# SCH_Linefollowerv1_2022-10-21.net
KiCad netlist of a schematic drawn in EasyEDA
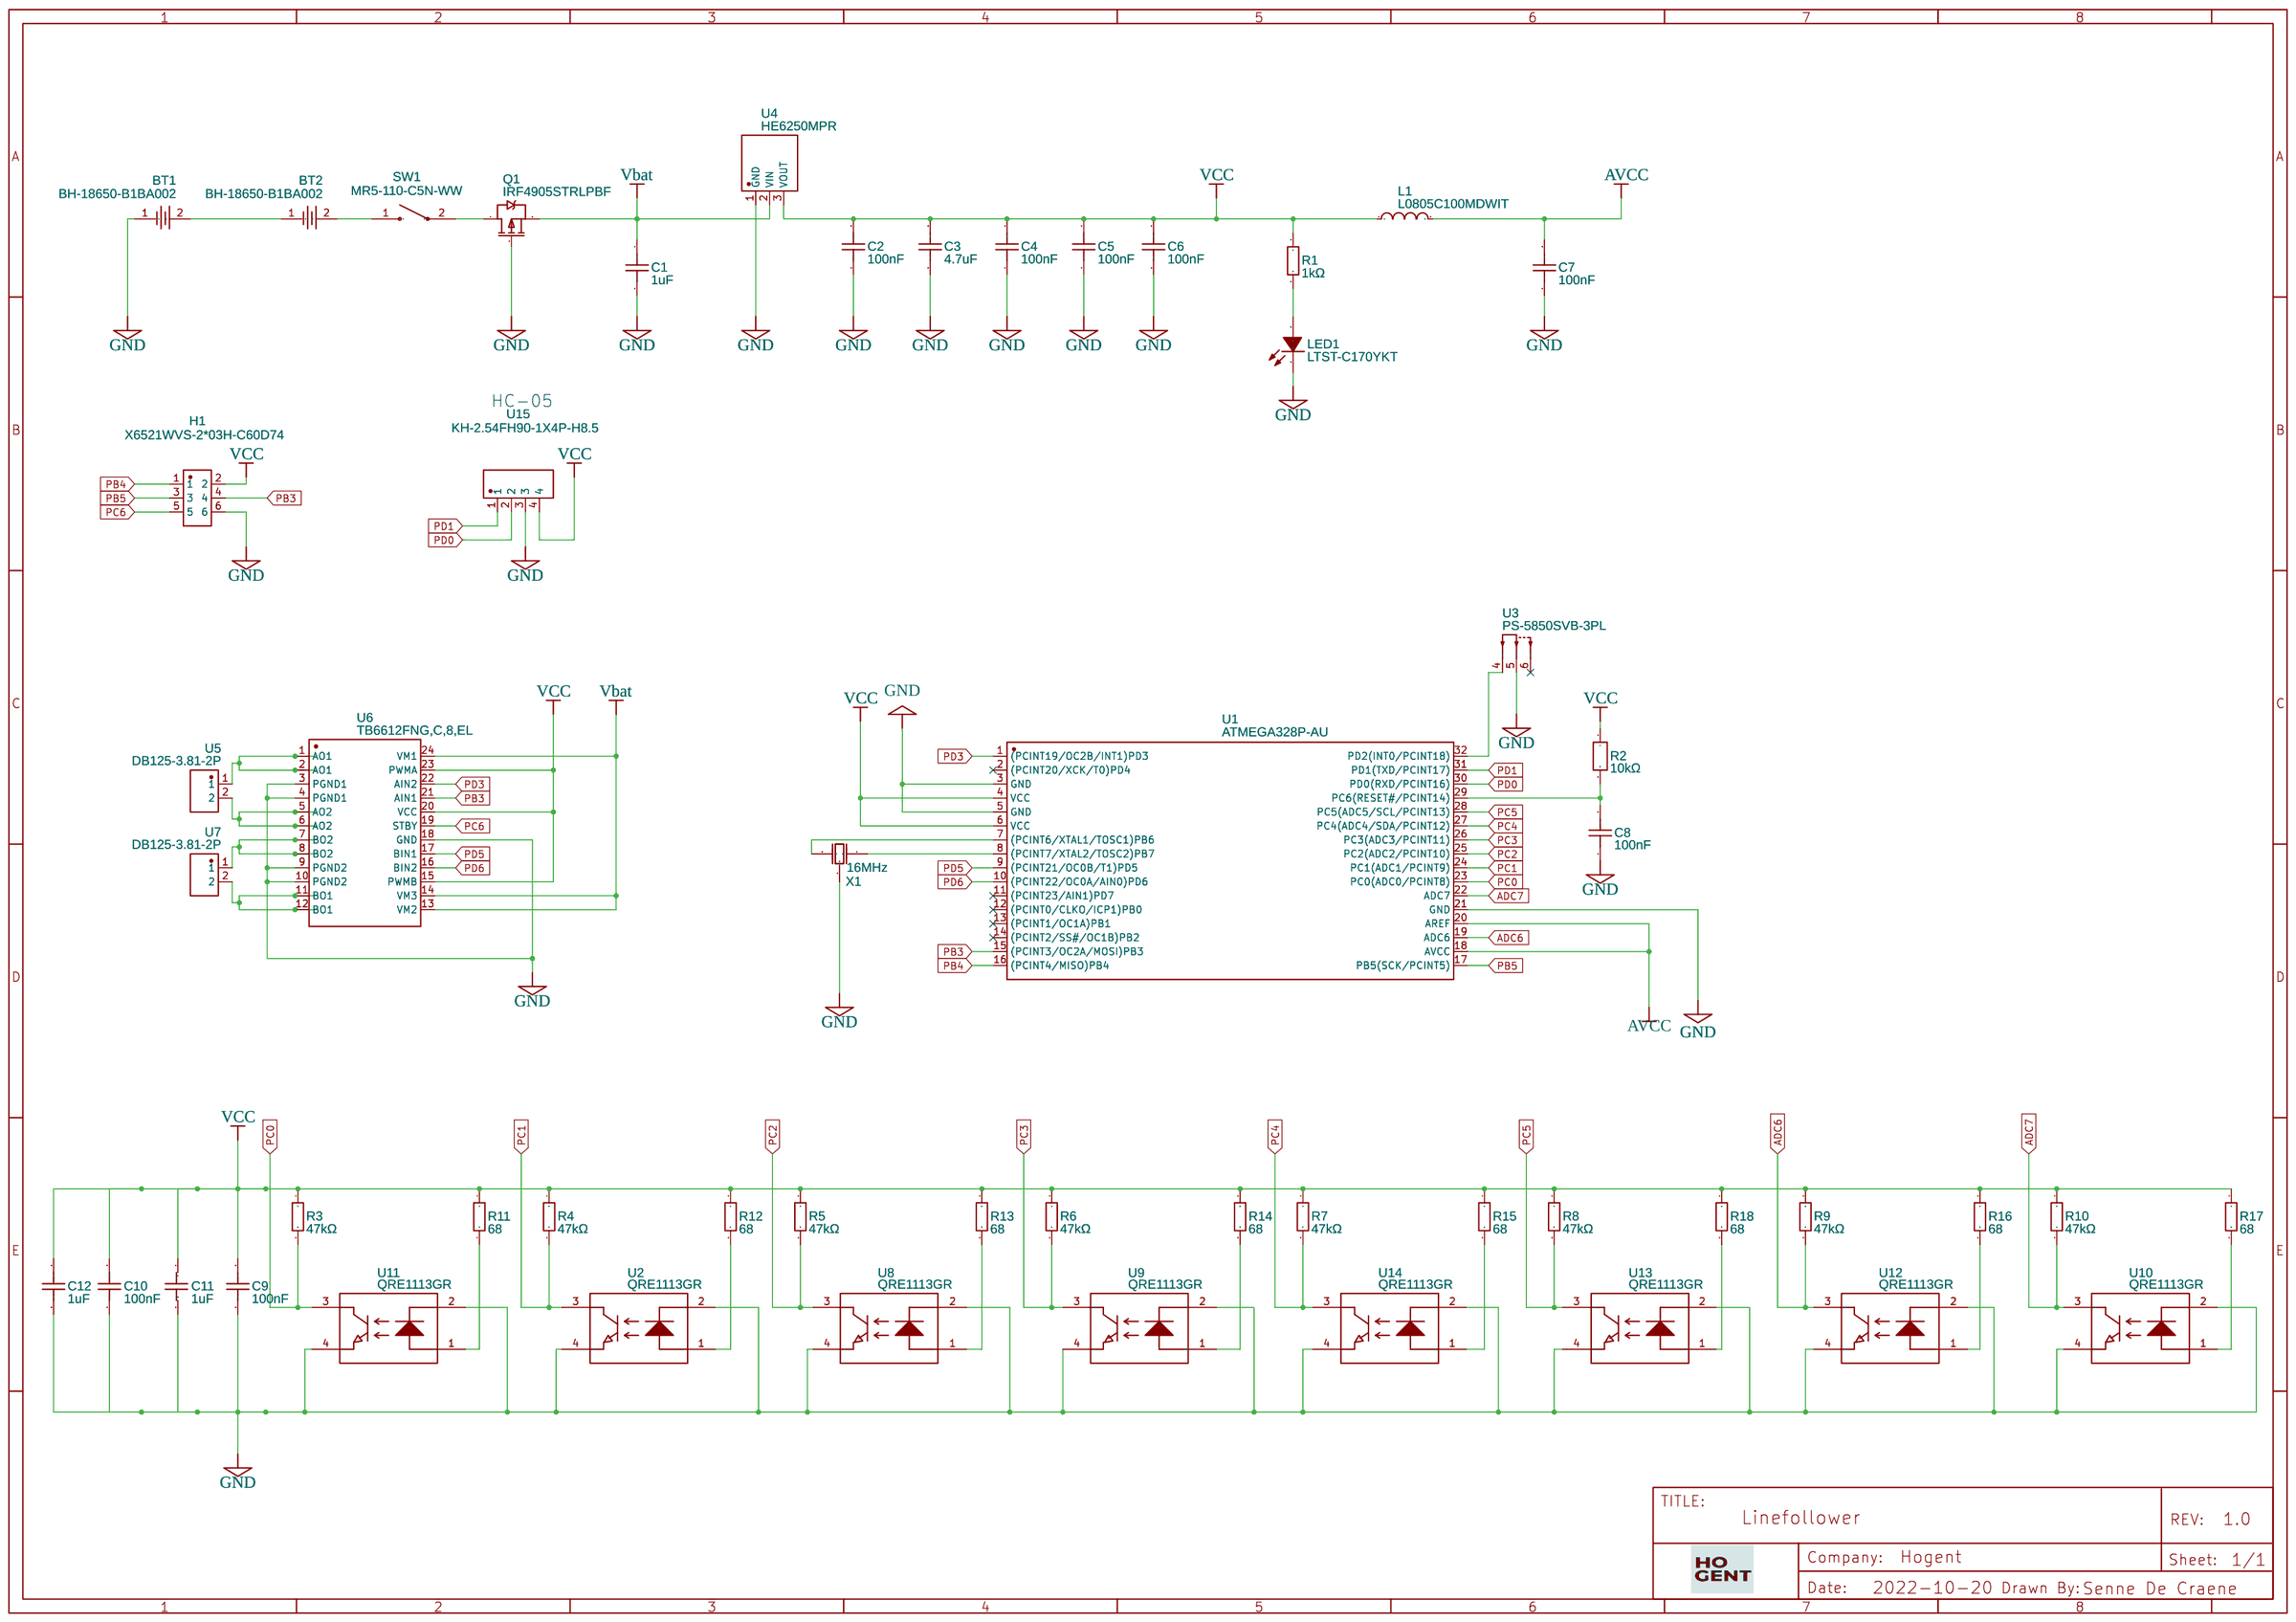
[diagram p0: schematic sheet]

(export (version "E")
  (design (tool "Eeschema 10.0.6"))
  (components
    (comp (ref "BT1")
      (value "BH-18650-B1BA002")
      (fields (field (name "BOM_Supplier Part") "C2988620"))
      (libsource (lib "") (part "BH-18650-B1BA002"))
    )
    (comp (ref "BT2")
      (value "BH-18650-B1BA002")
      (fields (field (name "BOM_Supplier Part") "C2988620"))
      (libsource (lib "") (part "BH-18650-B1BA002"))
    )
    (comp (ref "C1")
      (value "1uF")
      (fields
        (field (name "BOM_Manufacturer Part") "LMK212BJ105KD-T")
        (field (name "BOM_Supplier Part") "C92812")
      )
      (libsource (lib "") (part "LMK212BJ105KD-T_1"))
    )
    (comp (ref "C2")
      (value "100nF")
      (fields
        (field (name "BOM_Manufacturer Part") "LMK212SD104KG-T")
        (field (name "BOM_Supplier Part") "C386062")
      )
      (libsource (lib "") (part "LMK212SD104KG-T"))
    )
    (comp (ref "C3")
      (value "4.7uF")
      (fields
        (field (name "BOM_Manufacturer Part") "GCM21BC71A475KA73L")
        (field (name "BOM_Supplier Part") "C126583")
      )
      (libsource (lib "") (part "GCM21BC71A475KA73L"))
    )
    (comp (ref "C4")
      (value "100nF")
      (fields
        (field (name "BOM_Manufacturer Part") "LMK212SD104KG-T")
        (field (name "BOM_Supplier Part") "C386062")
      )
      (libsource (lib "") (part "LMK212SD104KG-T"))
    )
    (comp (ref "C5")
      (value "100nF")
      (fields
        (field (name "BOM_Manufacturer Part") "LMK212SD104KG-T")
        (field (name "BOM_Supplier Part") "C386062")
      )
      (libsource (lib "") (part "LMK212SD104KG-T"))
    )
    (comp (ref "C6")
      (value "100nF")
      (fields
        (field (name "BOM_Manufacturer Part") "LMK212SD104KG-T")
        (field (name "BOM_Supplier Part") "C386062")
      )
      (libsource (lib "") (part "LMK212SD104KG-T"))
    )
    (comp (ref "C7")
      (value "100nF")
      (fields
        (field (name "BOM_Manufacturer Part") "LMK212SD104KG-T")
        (field (name "BOM_Supplier Part") "C386062")
      )
      (libsource (lib "") (part "LMK212SD104KG-T"))
    )
    (comp (ref "C8")
      (value "100nF")
      (fields
        (field (name "BOM_Manufacturer Part") "LMK212SD104KG-T")
        (field (name "BOM_Supplier Part") "C386062")
      )
      (libsource (lib "") (part "LMK212SD104KG-T"))
    )
    (comp (ref "C9")
      (value "100nF")
      (fields
        (field (name "BOM_Manufacturer Part") "LMK212SD104KG-T")
        (field (name "BOM_Supplier Part") "C386062")
      )
      (libsource (lib "") (part "LMK212SD104KG-T"))
    )
    (comp (ref "C10")
      (value "100nF")
      (fields
        (field (name "BOM_Manufacturer Part") "LMK212SD104KG-T")
        (field (name "BOM_Supplier Part") "C386062")
      )
      (libsource (lib "") (part "LMK212SD104KG-T"))
    )
    (comp (ref "C11")
      (value "1uF")
      (fields
        (field (name "BOM_Manufacturer Part") "LMK212BJ105KD-T")
        (field (name "BOM_Supplier Part") "C92812")
      )
      (libsource (lib "") (part "LMK212BJ105KD-T"))
    )
    (comp (ref "C12")
      (value "1uF")
      (fields
        (field (name "BOM_Manufacturer Part") "LMK212BJ105KD-T")
        (field (name "BOM_Supplier Part") "C92812")
      )
      (libsource (lib "") (part "LMK212BJ105KD-T_1"))
    )
    (comp (ref "H1")
      (value "X6521WVS-2*03H-C60D74")
      (fields (field (name "BOM_Supplier Part") "C780054"))
      (libsource (lib "") (part "X6521WVS-2*03H-C60D74"))
    )
    (comp (ref "L1")
      (value "L0805C100MDWIT")
      (fields (field (name "BOM_Supplier Part") "C696787"))
      (libsource (lib "") (part "L0805C100MDWIT"))
    )
    (comp (ref "LED1")
      (value "LTST-C170YKT")
      (fields (field (name "BOM_Supplier Part") "C125092"))
      (libsource (lib "") (part "LTST-C170YKT"))
    )
    (comp (ref "Q1")
      (value "IRF4905STRLPBF")
      (fields (field (name "BOM_Supplier Part") "C2620"))
      (libsource (lib "") (part "IRF4905STRLPBF"))
    )
    (comp (ref "R1")
      (value "1kΩ")
      (fields
        (field (name "BOM_Manufacturer Part") "ARG05BTC1001")
        (field (name "BOM_Supplier Part") "C309081")
      )
      (libsource (lib "") (part "ARG05BTC1001"))
    )
    (comp (ref "R2")
      (value "10kΩ")
      (fields
        (field (name "BOM_Manufacturer Part") "ARG05BTC1002")
        (field (name "BOM_Supplier Part") "C406725")
      )
      (libsource (lib "") (part "ARG05BTC1002"))
    )
    (comp (ref "R3")
      (value "47kΩ")
      (fields
        (field (name "BOM_Manufacturer Part") "AECR0805F47K0K9")
        (field (name "BOM_Supplier Part") "C328397")
      )
      (libsource (lib "") (part "AECR0805F47K0K9"))
    )
    (comp (ref "R4")
      (value "47kΩ")
      (fields
        (field (name "BOM_Manufacturer Part") "AECR0805F47K0K9")
        (field (name "BOM_Supplier Part") "C328397")
      )
      (libsource (lib "") (part "AECR0805F47K0K9"))
    )
    (comp (ref "R5")
      (value "47kΩ")
      (fields
        (field (name "BOM_Manufacturer Part") "AECR0805F47K0K9")
        (field (name "BOM_Supplier Part") "C328397")
      )
      (libsource (lib "") (part "AECR0805F47K0K9"))
    )
    (comp (ref "R6")
      (value "47kΩ")
      (fields
        (field (name "BOM_Manufacturer Part") "AECR0805F47K0K9")
        (field (name "BOM_Supplier Part") "C328397")
      )
      (libsource (lib "") (part "AECR0805F47K0K9"))
    )
    (comp (ref "R7")
      (value "47kΩ")
      (fields
        (field (name "BOM_Manufacturer Part") "AECR0805F47K0K9")
        (field (name "BOM_Supplier Part") "C328397")
      )
      (libsource (lib "") (part "AECR0805F47K0K9"))
    )
    (comp (ref "R8")
      (value "47kΩ")
      (fields
        (field (name "BOM_Manufacturer Part") "AECR0805F47K0K9")
        (field (name "BOM_Supplier Part") "C328397")
      )
      (libsource (lib "") (part "AECR0805F47K0K9"))
    )
    (comp (ref "R9")
      (value "47kΩ")
      (fields
        (field (name "BOM_Manufacturer Part") "AECR0805F47K0K9")
        (field (name "BOM_Supplier Part") "C328397")
      )
      (libsource (lib "") (part "AECR0805F47K0K9"))
    )
    (comp (ref "R10")
      (value "47kΩ")
      (fields
        (field (name "BOM_Manufacturer Part") "AECR0805F47K0K9")
        (field (name "BOM_Supplier Part") "C328397")
      )
      (libsource (lib "") (part "AECR0805F47K0K9"))
    )
    (comp (ref "R11")
      (value "68")
      (fields
        (field (name "BOM_Manufacturer Part") "RC0805FR-0768RL")
        (field (name "BOM_Supplier Part") "C137498")
      )
      (libsource (lib "") (part "RC0805FR-0768RL"))
    )
    (comp (ref "R12")
      (value "68")
      (fields
        (field (name "BOM_Manufacturer Part") "RC0805FR-0768RL")
        (field (name "BOM_Supplier Part") "C137498")
      )
      (libsource (lib "") (part "RC0805FR-0768RL"))
    )
    (comp (ref "R13")
      (value "68")
      (fields
        (field (name "BOM_Manufacturer Part") "RC0805FR-0768RL")
        (field (name "BOM_Supplier Part") "C137498")
      )
      (libsource (lib "") (part "RC0805FR-0768RL"))
    )
    (comp (ref "R14")
      (value "68")
      (fields
        (field (name "BOM_Manufacturer Part") "RC0805FR-0768RL")
        (field (name "BOM_Supplier Part") "C137498")
      )
      (libsource (lib "") (part "RC0805FR-0768RL"))
    )
    (comp (ref "R15")
      (value "68")
      (fields
        (field (name "BOM_Manufacturer Part") "RC0805FR-0768RL")
        (field (name "BOM_Supplier Part") "C137498")
      )
      (libsource (lib "") (part "RC0805FR-0768RL"))
    )
    (comp (ref "R16")
      (value "68")
      (fields
        (field (name "BOM_Manufacturer Part") "RC0805FR-0768RL")
        (field (name "BOM_Supplier Part") "C137498")
      )
      (libsource (lib "") (part "RC0805FR-0768RL"))
    )
    (comp (ref "R17")
      (value "68")
      (fields
        (field (name "BOM_Manufacturer Part") "RC0805FR-0768RL")
        (field (name "BOM_Supplier Part") "C137498")
      )
      (libsource (lib "") (part "RC0805FR-0768RL"))
    )
    (comp (ref "R18")
      (value "68")
      (fields
        (field (name "BOM_Manufacturer Part") "RC0805FR-0768RL")
        (field (name "BOM_Supplier Part") "C137498")
      )
      (libsource (lib "") (part "RC0805FR-0768RL"))
    )
    (comp (ref "SW1")
      (value "MR5-110-C5N-WW")
      (fields (field (name "BOM_Supplier Part") "C2829507"))
      (libsource (lib "") (part "MR5-110-C5N-WW"))
    )
    (comp (ref "U1")
      (value "ATMEGA328P-AU")
      (fields (field (name "BOM_Supplier Part") "C14877"))
      (libsource (lib "") (part "ATMEGA328P-AU"))
    )
    (comp (ref "U2")
      (value "QRE1113GR")
      (fields (field (name "BOM_Supplier Part") "C232862"))
      (libsource (lib "") (part "QRE1113GR_1"))
    )
    (comp (ref "U3")
      (value "PS-5850SVB-3PL")
      (fields (field (name "BOM_Supplier Part") "C5159077"))
      (libsource (lib "") (part "PS-5850SVB-3PL"))
    )
    (comp (ref "U4")
      (value "HE6250MPR")
      (fields (field (name "BOM_Supplier Part") "C711940"))
      (libsource (lib "") (part "HE6250MPR"))
    )
    (comp (ref "U5")
      (value "DB125-3.81-2P")
      (fields (field (name "BOM_Supplier Part") "C395878"))
      (libsource (lib "") (part "DB125-3.81-2P"))
    )
    (comp (ref "U6")
      (value "TB6612FNG,C,8,EL")
      (fields (field (name "BOM_Supplier Part") "C141517"))
      (libsource (lib "") (part "Unknown_500_-570"))
    )
    (comp (ref "U7")
      (value "DB125-3.81-2P")
      (fields (field (name "BOM_Supplier Part") "C395878"))
      (libsource (lib "") (part "DB125-3.81-2P"))
    )
    (comp (ref "U8")
      (value "QRE1113GR")
      (fields (field (name "BOM_Supplier Part") "C232862"))
      (libsource (lib "") (part "QRE1113GR_2"))
    )
    (comp (ref "U9")
      (value "QRE1113GR")
      (fields (field (name "BOM_Supplier Part") "C232862"))
      (libsource (lib "") (part "QRE1113GR_3"))
    )
    (comp (ref "U10")
      (value "QRE1113GR")
      (fields (field (name "BOM_Supplier Part") "C232862"))
      (libsource (lib "") (part "QRE1113GR_4"))
    )
    (comp (ref "U11")
      (value "QRE1113GR")
      (fields (field (name "BOM_Supplier Part") "C232862"))
      (libsource (lib "") (part "QRE1113GR_4"))
    )
    (comp (ref "U12")
      (value "QRE1113GR")
      (fields (field (name "BOM_Supplier Part") "C232862"))
      (libsource (lib "") (part "QRE1113GR_5"))
    )
    (comp (ref "U13")
      (value "QRE1113GR")
      (fields (field (name "BOM_Supplier Part") "C232862"))
      (libsource (lib "") (part "QRE1113GR"))
    )
    (comp (ref "U14")
      (value "QRE1113GR")
      (fields (field (name "BOM_Supplier Part") "C232862"))
      (libsource (lib "") (part "QRE1113GR_6"))
    )
    (comp (ref "U15")
      (value "KH-2.54FH90-1X4P-H8.5")
      (fields (field (name "BOM_Supplier Part") "C2932680"))
      (libsource (lib "") (part "KH-2.54FH90-1X4P-H8.5"))
    )
    (comp (ref "X1")
      (value "16MHz")
      (fields
        (field (name "BOM_Manufacturer Part") "CSTNE16M0V53C000R0")
        (field (name "BOM_Supplier Part") "C882606")
      )
      (libsource (lib "") (part "CSTNE16M0V53C000R0"))
    )
  )
  (nets
    (net (code "1") (name "ADC6") (class "Default")
      (node (ref "R9") (pin "2") (pinfunction "2_2") (pintype "unspecified"))
      (node (ref "U1") (pin "19") (pinfunction "ADC6_19") (pintype "unspecified"))
      (node (ref "U12") (pin "3") (pinfunction "3_3") (pintype "input"))
    )
    (net (code "2") (name "ADC7") (class "Default")
      (node (ref "R10") (pin "2") (pinfunction "2_2") (pintype "unspecified"))
      (node (ref "U1") (pin "22") (pinfunction "ADC7_22") (pintype "unspecified"))
      (node (ref "U10") (pin "3") (pinfunction "3_3") (pintype "input"))
    )
    (net (code "3") (name "AVCC") (class "Default")
      (node (ref "C7") (pin "2") (pinfunction "2_2") (pintype "unspecified"))
      (node (ref "L1") (pin "2") (pinfunction "2_2") (pintype "unspecified"))
      (node (ref "U1") (pin "18") (pinfunction "AVCC_18") (pintype "unspecified"))
      (node (ref "U1") (pin "20") (pinfunction "AREF_20") (pintype "unspecified"))
    )
    (net (code "4") (name "GND") (class "Default")
      (node (ref "BT1") (pin "1") (pinfunction "1_1") (pintype "input"))
      (node (ref "C1") (pin "2") (pinfunction "2_2") (pintype "unspecified"))
      (node (ref "C10") (pin "1") (pinfunction "1_1") (pintype "unspecified"))
      (node (ref "C11") (pin "2") (pinfunction "2_2") (pintype "unspecified"))
      (node (ref "C12") (pin "2") (pinfunction "2_2") (pintype "unspecified"))
      (node (ref "C2") (pin "1") (pinfunction "1_1") (pintype "unspecified"))
      (node (ref "C3") (pin "1") (pinfunction "1_1") (pintype "unspecified"))
      (node (ref "C4") (pin "1") (pinfunction "1_1") (pintype "unspecified"))
      (node (ref "C5") (pin "1") (pinfunction "1_1") (pintype "unspecified"))
      (node (ref "C6") (pin "1") (pinfunction "1_1") (pintype "unspecified"))
      (node (ref "C7") (pin "1") (pinfunction "1_1") (pintype "unspecified"))
      (node (ref "C8") (pin "1") (pinfunction "1_1") (pintype "unspecified"))
      (node (ref "C9") (pin "1") (pinfunction "1_1") (pintype "unspecified"))
      (node (ref "H1") (pin "6") (pinfunction "6_6") (pintype "unspecified"))
      (node (ref "LED1") (pin "1") (pinfunction "1_1") (pintype "unspecified"))
      (node (ref "Q1") (pin "1") (pinfunction "G_1") (pintype "unspecified"))
      (node (ref "U1") (pin "21") (pinfunction "GND_21") (pintype "unspecified"))
      (node (ref "U1") (pin "3") (pinfunction "GND_3") (pintype "unspecified"))
      (node (ref "U1") (pin "5") (pinfunction "GND_5") (pintype "unspecified"))
      (node (ref "U10") (pin "2") (pinfunction "2_2") (pintype "input"))
      (node (ref "U10") (pin "4") (pinfunction "4_4") (pintype "input"))
      (node (ref "U11") (pin "2") (pinfunction "2_2") (pintype "input"))
      (node (ref "U11") (pin "4") (pinfunction "4_4") (pintype "input"))
      (node (ref "U12") (pin "2") (pinfunction "2_2") (pintype "input"))
      (node (ref "U12") (pin "4") (pinfunction "4_4") (pintype "input"))
      (node (ref "U13") (pin "2") (pinfunction "2_2") (pintype "input"))
      (node (ref "U13") (pin "4") (pinfunction "4_4") (pintype "input"))
      (node (ref "U14") (pin "2") (pinfunction "2_2") (pintype "input"))
      (node (ref "U14") (pin "4") (pinfunction "4_4") (pintype "input"))
      (node (ref "U15") (pin "3") (pinfunction "3_3") (pintype "unspecified"))
      (node (ref "U2") (pin "2") (pinfunction "2_2") (pintype "input"))
      (node (ref "U2") (pin "4") (pinfunction "4_4") (pintype "input"))
      (node (ref "U3") (pin "5") (pinfunction "5_5") (pintype "unspecified"))
      (node (ref "U4") (pin "1") (pinfunction "GND_1") (pintype "unspecified"))
      (node (ref "U6") (pin "10") (pinfunction "PGND2_10") (pintype "unspecified"))
      (node (ref "U6") (pin "18") (pinfunction "GND_18") (pintype "unspecified"))
      (node (ref "U6") (pin "3") (pinfunction "PGND1_3") (pintype "unspecified"))
      (node (ref "U6") (pin "4") (pinfunction "PGND1_4") (pintype "unspecified"))
      (node (ref "U6") (pin "9") (pinfunction "PGND2_9") (pintype "unspecified"))
      (node (ref "U8") (pin "2") (pinfunction "2_2") (pintype "input"))
      (node (ref "U8") (pin "4") (pinfunction "4_4") (pintype "input"))
      (node (ref "U9") (pin "2") (pinfunction "2_2") (pintype "input"))
      (node (ref "U9") (pin "4") (pinfunction "4_4") (pintype "input"))
      (node (ref "X1") (pin "2") (pinfunction "GND_2") (pintype "input"))
    )
    (net (code "5") (name "Net-(BT1-Pad2)") (class "Default")
      (node (ref "BT1") (pin "2") (pinfunction "2_2") (pintype "input"))
      (node (ref "BT2") (pin "1") (pinfunction "1_1") (pintype "input"))
    )
    (net (code "6") (name "Net-(BT2-Pad2)") (class "Default")
      (node (ref "BT2") (pin "2") (pinfunction "2_2") (pintype "input"))
      (node (ref "SW1") (pin "1") (pinfunction "1_1") (pintype "unspecified"))
    )
    (net (code "7") (name "Net-(LED1-Pad2)") (class "Default")
      (node (ref "LED1") (pin "2") (pinfunction "2_2") (pintype "unspecified"))
      (node (ref "R1") (pin "2") (pinfunction "2_2") (pintype "unspecified"))
    )
    (net (code "8") (name "Net-(Q1-D)") (class "Default")
      (node (ref "Q1") (pin "4") (pinfunction "D_4") (pintype "unspecified"))
      (node (ref "SW1") (pin "2") (pinfunction "2_2") (pintype "unspecified"))
    )
    (net (code "9") (name "Net-(R11-Pad2)") (class "Default")
      (node (ref "R11") (pin "2") (pinfunction "2_2") (pintype "input"))
      (node (ref "U11") (pin "1") (pinfunction "1_1") (pintype "input"))
    )
    (net (code "10") (name "Net-(R12-Pad2)") (class "Default")
      (node (ref "R12") (pin "2") (pinfunction "2_2") (pintype "input"))
      (node (ref "U2") (pin "1") (pinfunction "1_1") (pintype "input"))
    )
    (net (code "11") (name "Net-(R13-Pad2)") (class "Default")
      (node (ref "R13") (pin "2") (pinfunction "2_2") (pintype "input"))
      (node (ref "U8") (pin "1") (pinfunction "1_1") (pintype "input"))
    )
    (net (code "12") (name "Net-(R14-Pad2)") (class "Default")
      (node (ref "R14") (pin "2") (pinfunction "2_2") (pintype "input"))
      (node (ref "U9") (pin "1") (pinfunction "1_1") (pintype "input"))
    )
    (net (code "13") (name "Net-(R15-Pad2)") (class "Default")
      (node (ref "R15") (pin "2") (pinfunction "2_2") (pintype "input"))
      (node (ref "U14") (pin "1") (pinfunction "1_1") (pintype "input"))
    )
    (net (code "14") (name "Net-(R16-Pad2)") (class "Default")
      (node (ref "R16") (pin "2") (pinfunction "2_2") (pintype "input"))
      (node (ref "U12") (pin "1") (pinfunction "1_1") (pintype "input"))
    )
    (net (code "15") (name "Net-(R17-Pad2)") (class "Default")
      (node (ref "R17") (pin "2") (pinfunction "2_2") (pintype "input"))
      (node (ref "U10") (pin "1") (pinfunction "1_1") (pintype "input"))
    )
    (net (code "16") (name "Net-(R18-Pad2)") (class "Default")
      (node (ref "R18") (pin "2") (pinfunction "2_2") (pintype "input"))
      (node (ref "U13") (pin "1") (pinfunction "1_1") (pintype "input"))
    )
    (net (code "17") (name "Net-(U1-(PCINT6{slash}XTAL1{slash}TOSC1)PB6)") (class "Default")
      (node (ref "U1") (pin "7") (pinfunction "(PCINT6/XTAL1/TOSC1)PB6_7") (pintype "unspecified"))
      (node (ref "X1") (pin "3") (pinfunction "OSC2_3") (pintype "input"))
    )
    (net (code "18") (name "Net-(U1-(PCINT7{slash}XTAL2{slash}TOSC2)PB7)") (class "Default")
      (node (ref "U1") (pin "8") (pinfunction "(PCINT7/XTAL2/TOSC2)PB7_8") (pintype "unspecified"))
      (node (ref "X1") (pin "1") (pinfunction "OSC1_1") (pintype "input"))
    )
    (net (code "19") (name "Net-(U1-PC6(RESET#{slash}PCINT14))") (class "Default")
      (node (ref "C8") (pin "2") (pinfunction "2_2") (pintype "unspecified"))
      (node (ref "R2") (pin "2") (pinfunction "2_2") (pintype "unspecified"))
      (node (ref "U1") (pin "29") (pinfunction "PC6(RESET#/PCINT14)_29") (pintype "unspecified"))
    )
    (net (code "20") (name "Net-(U1-PD2(INT0{slash}PCINT18))") (class "Default")
      (node (ref "U1") (pin "32") (pinfunction "PD2(INT0/PCINT18)_32") (pintype "unspecified"))
      (node (ref "U3") (pin "4") (pinfunction "4_4") (pintype "unspecified"))
    )
    (net (code "21") (name "Net-(U5-Pad1)") (class "Default")
      (node (ref "U5") (pin "1") (pinfunction "1_1") (pintype "unspecified"))
      (node (ref "U6") (pin "1") (pinfunction "AO1_1") (pintype "unspecified"))
      (node (ref "U6") (pin "2") (pinfunction "AO1_2") (pintype "unspecified"))
    )
    (net (code "22") (name "Net-(U5-Pad2)") (class "Default")
      (node (ref "U5") (pin "2") (pinfunction "2_2") (pintype "unspecified"))
      (node (ref "U6") (pin "5") (pinfunction "AO2_5") (pintype "unspecified"))
      (node (ref "U6") (pin "6") (pinfunction "AO2_6") (pintype "unspecified"))
    )
    (net (code "23") (name "Net-(U6-BO1-Pad11)") (class "Default")
      (node (ref "U6") (pin "11") (pinfunction "BO1_11") (pintype "unspecified"))
      (node (ref "U6") (pin "12") (pinfunction "BO1_12") (pintype "unspecified"))
      (node (ref "U7") (pin "2") (pinfunction "2_2") (pintype "unspecified"))
    )
    (net (code "24") (name "Net-(U6-BO2-Pad7)") (class "Default")
      (node (ref "U6") (pin "7") (pinfunction "BO2_7") (pintype "unspecified"))
      (node (ref "U6") (pin "8") (pinfunction "BO2_8") (pintype "unspecified"))
      (node (ref "U7") (pin "1") (pinfunction "1_1") (pintype "unspecified"))
    )
    (net (code "25") (name "PB3") (class "Default")
      (node (ref "H1") (pin "4") (pinfunction "4_4") (pintype "unspecified"))
      (node (ref "U1") (pin "15") (pinfunction "(PCINT3/OC2A/MOSI)PB3_15") (pintype "unspecified"))
      (node (ref "U6") (pin "21") (pinfunction "AIN1_21") (pintype "unspecified"))
    )
    (net (code "26") (name "PB4") (class "Default")
      (node (ref "H1") (pin "1") (pinfunction "1_1") (pintype "unspecified"))
      (node (ref "U1") (pin "16") (pinfunction "(PCINT4/MISO)PB4_16") (pintype "unspecified"))
    )
    (net (code "27") (name "PB5") (class "Default")
      (node (ref "H1") (pin "3") (pinfunction "3_3") (pintype "unspecified"))
      (node (ref "U1") (pin "17") (pinfunction "PB5(SCK/PCINT5)_17") (pintype "unspecified"))
    )
    (net (code "28") (name "PC0") (class "Default")
      (node (ref "R3") (pin "2") (pinfunction "2_2") (pintype "unspecified"))
      (node (ref "U1") (pin "23") (pinfunction "PC0(ADC0/PCINT8)_23") (pintype "unspecified"))
      (node (ref "U11") (pin "3") (pinfunction "3_3") (pintype "input"))
    )
    (net (code "29") (name "PC1") (class "Default")
      (node (ref "R4") (pin "2") (pinfunction "2_2") (pintype "unspecified"))
      (node (ref "U1") (pin "24") (pinfunction "PC1(ADC1/PCINT9)_24") (pintype "unspecified"))
      (node (ref "U2") (pin "3") (pinfunction "3_3") (pintype "input"))
    )
    (net (code "30") (name "PC2") (class "Default")
      (node (ref "R5") (pin "2") (pinfunction "2_2") (pintype "unspecified"))
      (node (ref "U1") (pin "25") (pinfunction "PC2(ADC2/PCINT10)_25") (pintype "unspecified"))
      (node (ref "U8") (pin "3") (pinfunction "3_3") (pintype "input"))
    )
    (net (code "31") (name "PC3") (class "Default")
      (node (ref "R6") (pin "2") (pinfunction "2_2") (pintype "unspecified"))
      (node (ref "U1") (pin "26") (pinfunction "PC3(ADC3/PCINT11)_26") (pintype "unspecified"))
      (node (ref "U9") (pin "3") (pinfunction "3_3") (pintype "input"))
    )
    (net (code "32") (name "PC4") (class "Default")
      (node (ref "R7") (pin "2") (pinfunction "2_2") (pintype "unspecified"))
      (node (ref "U1") (pin "27") (pinfunction "PC4(ADC4/SDA/PCINT12)_27") (pintype "unspecified"))
      (node (ref "U14") (pin "3") (pinfunction "3_3") (pintype "input"))
    )
    (net (code "33") (name "PC5") (class "Default")
      (node (ref "R8") (pin "2") (pinfunction "2_2") (pintype "unspecified"))
      (node (ref "U1") (pin "28") (pinfunction "PC5(ADC5/SCL/PCINT13)_28") (pintype "unspecified"))
      (node (ref "U13") (pin "3") (pinfunction "3_3") (pintype "input"))
    )
    (net (code "34") (name "PC6") (class "Default")
      (node (ref "H1") (pin "5") (pinfunction "5_5") (pintype "unspecified"))
      (node (ref "U6") (pin "19") (pinfunction "STBY_19") (pintype "unspecified"))
    )
    (net (code "35") (name "PD0") (class "Default")
      (node (ref "U1") (pin "30") (pinfunction "PD0(RXD/PCINT16)_30") (pintype "unspecified"))
      (node (ref "U15") (pin "2") (pinfunction "2_2") (pintype "unspecified"))
    )
    (net (code "36") (name "PD1") (class "Default")
      (node (ref "U1") (pin "31") (pinfunction "PD1(TXD/PCINT17)_31") (pintype "unspecified"))
      (node (ref "U15") (pin "1") (pinfunction "1_1") (pintype "unspecified"))
    )
    (net (code "37") (name "PD3") (class "Default")
      (node (ref "U1") (pin "1") (pinfunction "(PCINT19/OC2B/INT1)PD3_1") (pintype "unspecified"))
      (node (ref "U6") (pin "22") (pinfunction "AIN2_22") (pintype "unspecified"))
    )
    (net (code "38") (name "PD5") (class "Default")
      (node (ref "U1") (pin "9") (pinfunction "(PCINT21/OC0B/T1)PD5_9") (pintype "unspecified"))
      (node (ref "U6") (pin "17") (pinfunction "BIN1_17") (pintype "unspecified"))
    )
    (net (code "39") (name "PD6") (class "Default")
      (node (ref "U1") (pin "10") (pinfunction "(PCINT22/OC0A/AIN0)PD6_10") (pintype "unspecified"))
      (node (ref "U6") (pin "16") (pinfunction "BIN2_16") (pintype "unspecified"))
    )
    (net (code "40") (name "VCC") (class "Default")
      (node (ref "C10") (pin "2") (pinfunction "2_2") (pintype "unspecified"))
      (node (ref "C11") (pin "1") (pinfunction "1_1") (pintype "unspecified"))
      (node (ref "C12") (pin "1") (pinfunction "1_1") (pintype "unspecified"))
      (node (ref "C2") (pin "2") (pinfunction "2_2") (pintype "unspecified"))
      (node (ref "C3") (pin "2") (pinfunction "2_2") (pintype "unspecified"))
      (node (ref "C4") (pin "2") (pinfunction "2_2") (pintype "unspecified"))
      (node (ref "C5") (pin "2") (pinfunction "2_2") (pintype "unspecified"))
      (node (ref "C6") (pin "2") (pinfunction "2_2") (pintype "unspecified"))
      (node (ref "C9") (pin "2") (pinfunction "2_2") (pintype "unspecified"))
      (node (ref "H1") (pin "2") (pinfunction "2_2") (pintype "unspecified"))
      (node (ref "L1") (pin "1") (pinfunction "1_1") (pintype "unspecified"))
      (node (ref "R1") (pin "1") (pinfunction "1_1") (pintype "unspecified"))
      (node (ref "R10") (pin "1") (pinfunction "1_1") (pintype "unspecified"))
      (node (ref "R11") (pin "1") (pinfunction "1_1") (pintype "input"))
      (node (ref "R12") (pin "1") (pinfunction "1_1") (pintype "input"))
      (node (ref "R13") (pin "1") (pinfunction "1_1") (pintype "input"))
      (node (ref "R14") (pin "1") (pinfunction "1_1") (pintype "input"))
      (node (ref "R15") (pin "1") (pinfunction "1_1") (pintype "input"))
      (node (ref "R16") (pin "1") (pinfunction "1_1") (pintype "input"))
      (node (ref "R17") (pin "1") (pinfunction "1_1") (pintype "input"))
      (node (ref "R18") (pin "1") (pinfunction "1_1") (pintype "input"))
      (node (ref "R2") (pin "1") (pinfunction "1_1") (pintype "unspecified"))
      (node (ref "R3") (pin "1") (pinfunction "1_1") (pintype "unspecified"))
      (node (ref "R4") (pin "1") (pinfunction "1_1") (pintype "unspecified"))
      (node (ref "R5") (pin "1") (pinfunction "1_1") (pintype "unspecified"))
      (node (ref "R6") (pin "1") (pinfunction "1_1") (pintype "unspecified"))
      (node (ref "R7") (pin "1") (pinfunction "1_1") (pintype "unspecified"))
      (node (ref "R8") (pin "1") (pinfunction "1_1") (pintype "unspecified"))
      (node (ref "R9") (pin "1") (pinfunction "1_1") (pintype "unspecified"))
      (node (ref "U1") (pin "4") (pinfunction "VCC_4") (pintype "unspecified"))
      (node (ref "U1") (pin "6") (pinfunction "VCC_6") (pintype "unspecified"))
      (node (ref "U15") (pin "4") (pinfunction "4_4") (pintype "unspecified"))
      (node (ref "U4") (pin "3") (pinfunction "VOUT_3") (pintype "unspecified"))
      (node (ref "U6") (pin "15") (pinfunction "PWMB_15") (pintype "unspecified"))
      (node (ref "U6") (pin "20") (pinfunction "VCC_20") (pintype "unspecified"))
      (node (ref "U6") (pin "23") (pinfunction "PWMA_23") (pintype "unspecified"))
    )
    (net (code "41") (name "Vbat") (class "Default")
      (node (ref "C1") (pin "1") (pinfunction "1_1") (pintype "unspecified"))
      (node (ref "Q1") (pin "3") (pinfunction "S_3") (pintype "unspecified"))
      (node (ref "U4") (pin "2") (pinfunction "VIN_2") (pintype "unspecified"))
      (node (ref "U6") (pin "13") (pinfunction "VM2_13") (pintype "unspecified"))
      (node (ref "U6") (pin "14") (pinfunction "VM3_14") (pintype "unspecified"))
      (node (ref "U6") (pin "24") (pinfunction "VM1_24") (pintype "unspecified"))
    )
    (net (code "42") (name "unconnected-(U1-(PCINT0{slash}CLKO{slash}ICP1)PB0-Pad12)") (class "Default")
      (node (ref "U1") (pin "12") (pinfunction "(PCINT0/CLKO/ICP1)PB0_12") (pintype "unspecified+no_connect"))
    )
    (net (code "43") (name "unconnected-(U1-(PCINT1{slash}OC1A)PB1-Pad13)") (class "Default")
      (node (ref "U1") (pin "13") (pinfunction "(PCINT1/OC1A)PB1_13") (pintype "unspecified+no_connect"))
    )
    (net (code "44") (name "unconnected-(U1-(PCINT2{slash}SS#{slash}OC1B)PB2-Pad14)") (class "Default")
      (node (ref "U1") (pin "14") (pinfunction "(PCINT2/SS#/OC1B)PB2_14") (pintype "unspecified+no_connect"))
    )
    (net (code "45") (name "unconnected-(U1-(PCINT20{slash}XCK{slash}T0)PD4-Pad2)") (class "Default")
      (node (ref "U1") (pin "2") (pinfunction "(PCINT20/XCK/T0)PD4_2") (pintype "unspecified+no_connect"))
    )
    (net (code "46") (name "unconnected-(U1-(PCINT23{slash}AIN1)PD7-Pad11)") (class "Default")
      (node (ref "U1") (pin "11") (pinfunction "(PCINT23/AIN1)PD7_11") (pintype "unspecified+no_connect"))
    )
    (net (code "47") (name "unconnected-(U3-Pad6)") (class "Default")
      (node (ref "U3") (pin "6") (pinfunction "6_6") (pintype "unspecified+no_connect"))
    )
  )
)
